# CPU_HDMI_PHY.net
KiCad netlist of a schematic drawn in Altium Designer
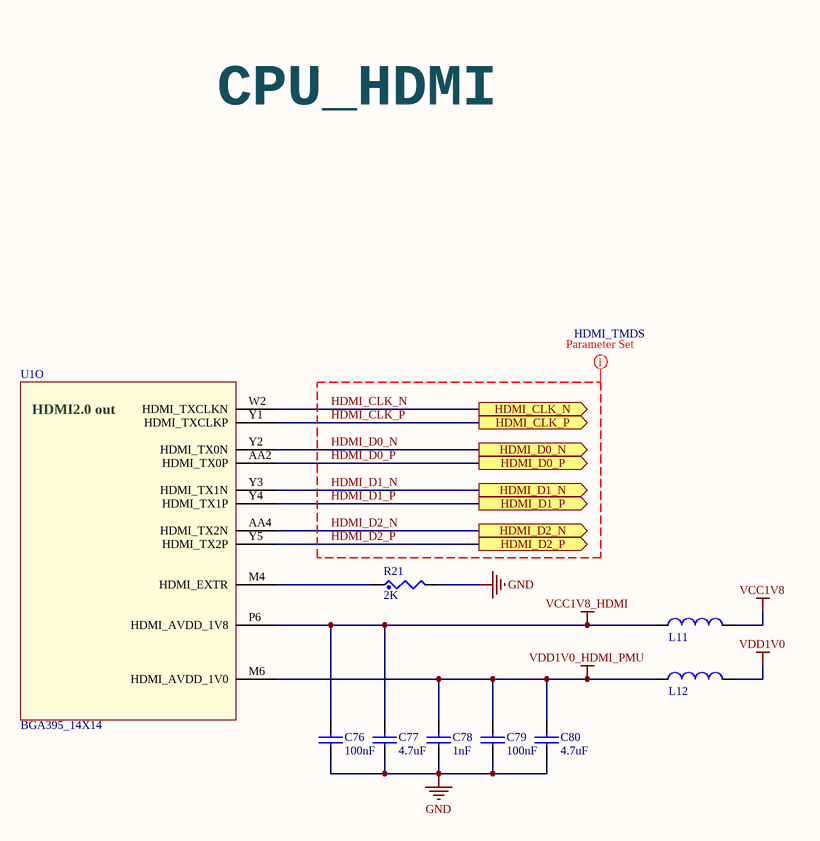
[diagram p0: CPU_HDMI_PHY.SchDoc]

(export (version "E")
  (design (tool "Eeschema 10.0.6"))
  (components
    (comp (ref "C76")
      (value "100nF")
      (footprint "0402_CC - C")
      (libsource (lib "AAR_RockChip_RK3328") (part "CAP_NP"))
    )
    (comp (ref "C77")
      (value "4.7uF")
      (footprint "0402_CC - C")
      (libsource (lib "AAR_RockChip_RK3328") (part "CAP_NP"))
    )
    (comp (ref "C78")
      (value "1nF")
      (footprint "0402_CC - C")
      (libsource (lib "AAR_RockChip_RK3328") (part "CAP_NP"))
    )
    (comp (ref "C79")
      (value "100nF")
      (footprint "0402_CC - C")
      (libsource (lib "AAR_RockChip_RK3328") (part "CAP_NP"))
    )
    (comp (ref "C80")
      (value "4.7uF")
      (footprint "0402_CC - C")
      (libsource (lib "AAR_RockChip_RK3328") (part "CAP_NP"))
    )
    (comp (ref "L11")
      (value "INDCHIP")
      (footprint "0603_C_Inductor")
      (description "Fixed Inductors  TDK, By AAR")
      (libsource (lib "AAR_RockChip_RK3328") (part "INDCHIP"))
    )
    (comp (ref "L12")
      (value "INDCHIP")
      (footprint "0603_C_Inductor")
      (description "Fixed Inductors  TDK, By AAR")
      (libsource (lib "AAR_RockChip_RK3328") (part "INDCHIP"))
    )
    (comp (ref "R21") (value "2K") (footprint "0402_CR") (libsource (lib "AAR_RockChip_RK3328") (part "RES")))
    (comp (ref "U1")
      (value "BGA395_14X14")
      (footprint "BGA395C65P21X21_1750X1750X117")
      (description "By AAR")
      (libsource (lib "AAR_RockChip_RK3328") (part "RK3328"))
    )
  )
  (nets
    (net (code "1") (name "/HDMI_CLK_N") (class "Default")
      (node (ref "U1") (pin "W2") (pinfunction "HDMI_TXCLKN_W2") (pintype "passive"))
    )
    (net (code "2") (name "/HDMI_CLK_P") (class "Default")
      (node (ref "U1") (pin "Y1") (pinfunction "HDMI_TXCLKP_Y1") (pintype "passive"))
    )
    (net (code "3") (name "/HDMI_D0_N") (class "Default")
      (node (ref "U1") (pin "Y2") (pinfunction "HDMI_TX0N_Y2") (pintype "passive"))
    )
    (net (code "4") (name "/HDMI_D0_P") (class "Default")
      (node (ref "U1") (pin "AA2") (pinfunction "HDMI_TX0P_AA2") (pintype "passive"))
    )
    (net (code "5") (name "/HDMI_D1_N") (class "Default")
      (node (ref "U1") (pin "Y3") (pinfunction "HDMI_TX1N_Y3") (pintype "passive"))
    )
    (net (code "6") (name "/HDMI_D1_P") (class "Default")
      (node (ref "U1") (pin "Y4") (pinfunction "HDMI_TX1P_Y4") (pintype "passive"))
    )
    (net (code "7") (name "/HDMI_D2_N") (class "Default")
      (node (ref "U1") (pin "AA4") (pinfunction "HDMI_TX2N_AA4") (pintype "passive"))
    )
    (net (code "8") (name "/HDMI_D2_P") (class "Default")
      (node (ref "U1") (pin "Y5") (pinfunction "HDMI_TX2P_Y5") (pintype "passive"))
    )
    (net (code "9") (name "GND") (class "Default")
      (node (ref "C76") (pin "2") (pinfunction "2_2") (pintype "passive"))
      (node (ref "C77") (pin "2") (pinfunction "2_2") (pintype "passive"))
      (node (ref "C78") (pin "2") (pinfunction "2_2") (pintype "passive"))
      (node (ref "C79") (pin "2") (pinfunction "2_2") (pintype "passive"))
      (node (ref "C80") (pin "2") (pinfunction "2_2") (pintype "passive"))
      (node (ref "R21") (pin "2") (pinfunction "2_2") (pintype "passive"))
    )
    (net (code "10") (name "Net-(U1O-HDMI_EXTR)") (class "Default")
      (node (ref "R21") (pin "1") (pinfunction "1_1") (pintype "passive"))
      (node (ref "U1") (pin "M4") (pinfunction "HDMI_EXTR_M4") (pintype "passive"))
    )
    (net (code "11") (name "VCC1V8") (class "Default")
      (node (ref "L11") (pin "2") (pinfunction "2_2") (pintype "passive"))
    )
    (net (code "12") (name "VCC1V8_HDMI") (class "Default")
      (node (ref "C76") (pin "1") (pinfunction "1_1") (pintype "passive"))
      (node (ref "C77") (pin "1") (pinfunction "1_1") (pintype "passive"))
      (node (ref "L11") (pin "1") (pinfunction "1_1") (pintype "passive"))
      (node (ref "U1") (pin "P6") (pinfunction "HDMI_AVDD_1V8_P6") (pintype "passive"))
    )
    (net (code "13") (name "VDD1V0") (class "Default")
      (node (ref "L12") (pin "2") (pinfunction "2_2") (pintype "passive"))
    )
    (net (code "14") (name "VDD1V0_HDMI_PMU") (class "Default")
      (node (ref "C78") (pin "1") (pinfunction "1_1") (pintype "passive"))
      (node (ref "C79") (pin "1") (pinfunction "1_1") (pintype "passive"))
      (node (ref "C80") (pin "1") (pinfunction "1_1") (pintype "passive"))
      (node (ref "L12") (pin "1") (pinfunction "1_1") (pintype "passive"))
      (node (ref "U1") (pin "M6") (pinfunction "HDMI_AVDD_1V0_M6") (pintype "passive"))
    )
  )
)
